# Game_of_Simon.net
KiCad netlist of a schematic drawn in Altium Designer
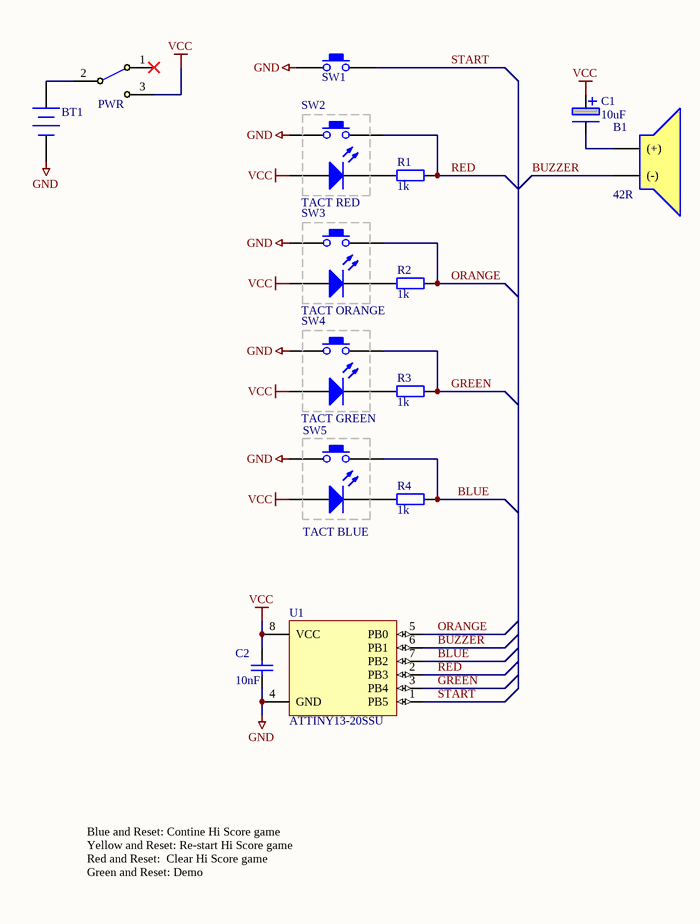
[diagram p0: Game of Simon.SchDoc]

(export (version "E")
  (design (tool "Eeschema 10.0.6"))
  (components
    (comp (ref "B1") (value "42R") (footprint "BUZZER") (libsource (lib "Simon Says") (part "BUZZER")))
    (comp (ref "BT1")
      (value "CR2032 Battery Holder")
      (footprint "Simon Says:CR2032 HOLDER")
      (description "CR2032 Battery Holder, Through Hole, Horizontal Mount")
      (libsource (lib "FavoritesLibrary") (part "SYM-19301741-1"))
    )
    (comp (ref "C1")
      (value "10uF")
      (footprint "Simon Says:CAP ELECTRO 5mm")
      (description "5mm Through Hole Electrolytic 2mm Pitch, 5mm height")
      (libsource (lib "FavoritesLibrary") (part "SYM-su2zmkw1kc3z49ns9isd-1"))
    )
    (comp (ref "C2")
      (value "10nF")
      (footprint "Simon Says:CAP 0.100\"")
      (description "Capacitor, Ceramic, 10000pF, 50VDC, 20-% Tol, 20+% Tol, X7R-TC Code, -15, 15%-TC")
      (fields (field (name "MANUFACTURER PART NUMBER") "C315C103M5R5TA"))
      (libsource (lib "FavoritesLibrary") (part "SYM-f9eb30fd1b76262c-1"))
    )
    (comp (ref "PWR")
      (value "SS12D00G3")
      (footprint "SS12D00G3")
      (description "SS12D00G3 Toggle Switch")
      (libsource (lib "Schlib1") (part "SS12D00G3 Toggle Switch"))
    )
    (comp (ref "R1")
      (value "1k")
      (footprint "Simon Says:RESISTOR 0.400\"")
      (description "RESISITOR THROUGH HOLE 1/4W")
      (libsource (lib "FavoritesLibrary") (part "SYM-iaxfckaaxq3jb0c9euu5-1"))
    )
    (comp (ref "R2")
      (value "1k")
      (footprint "Simon Says:RESISTOR 0.400\"")
      (description "RESISITOR THROUGH HOLE 1/4W")
      (libsource (lib "FavoritesLibrary") (part "SYM-iaxfckaaxq3jb0c9euu5-1"))
    )
    (comp (ref "R3")
      (value "1k")
      (footprint "Simon Says:RESISTOR 0.400\"")
      (description "RESISITOR THROUGH HOLE 1/4W")
      (libsource (lib "FavoritesLibrary") (part "SYM-iaxfckaaxq3jb0c9euu5-1"))
    )
    (comp (ref "R4")
      (value "1k")
      (footprint "Simon Says:RESISTOR 0.400\"")
      (description "RESISITOR THROUGH HOLE 1/4W")
      (libsource (lib "FavoritesLibrary") (part "SYM-iaxfckaaxq3jb0c9euu5-1"))
    )
    (comp (ref "SW1")
      (value "12MM TACT SWITCH")
      (footprint "12mm TACT THROUGH HOLE")
      (libsource (lib "Simon Says") (part "12MM TACT SWITCH"))
    )
    (comp (ref "SW2")
      (value "TACT RED")
      (footprint "ILLUMINATED TACT RED")
      (description "12mm TACT SWITCH RED")
      (libsource (lib "Simon Says") (part "TACT RED"))
    )
    (comp (ref "SW3")
      (value "TACT ORANGE")
      (footprint "ILLUMINATED TACT ORANGE")
      (description "12mm TACT SWITCH ORANGE")
      (libsource (lib "Simon Says") (part "TACT ORANGE"))
    )
    (comp (ref "SW4")
      (value "TACT GREEN")
      (footprint "ILLUMINATED TACT GREEN")
      (description "12mm TACT SWITCH GREEN")
      (libsource (lib "Simon Says") (part "TACT GREEN"))
    )
    (comp (ref "SW5")
      (value "TACT BLUE")
      (footprint "ILLUMINATED TACT BLUE")
      (description "ILLUMINATED 12MM TACT SWITCH (BLUE)")
      (libsource (lib "Simon Says") (part "TACT BLUE"))
    )
    (comp (ref "U1")
      (value "ATTINY13-20SSU")
      (footprint "DIP-8")
      (description "ATtiny Series 20 MHz 1 KB Flash 64 B SRAM 8-Bit Microcontroller - SOIC-8")
      (fields (field (name "MF") "Microchip"))
      (libsource (lib "Simon Says") (part "ATTINY13-20SSU"))
    )
  )
  (nets
    (net (code "1") (name "/BLUE") (class "Default")
      (node (ref "R4") (pin "2") (pinfunction "2_2") (pintype "passive"))
      (node (ref "SW5") (pin "2") (pinfunction "2_2") (pintype "passive"))
      (node (ref "U1") (pin "7") (pinfunction "PB2_7") (pintype "bidirectional"))
    )
    (net (code "2") (name "/BUZZER") (class "Default")
      (node (ref "B1") (pin "2") (pinfunction "(-)_2") (pintype "passive"))
      (node (ref "U1") (pin "6") (pinfunction "PB1_6") (pintype "bidirectional"))
    )
    (net (code "3") (name "/GREEN") (class "Default")
      (node (ref "R3") (pin "2") (pinfunction "2_2") (pintype "passive"))
      (node (ref "SW4") (pin "2") (pinfunction "2_2") (pintype "passive"))
      (node (ref "U1") (pin "3") (pinfunction "PB4_3") (pintype "bidirectional"))
    )
    (net (code "4") (name "/ORANGE") (class "Default")
      (node (ref "R2") (pin "2") (pinfunction "2_2") (pintype "passive"))
      (node (ref "SW3") (pin "2") (pinfunction "2_2") (pintype "passive"))
      (node (ref "U1") (pin "5") (pinfunction "PB0_5") (pintype "bidirectional"))
    )
    (net (code "5") (name "/RED") (class "Default")
      (node (ref "R1") (pin "2") (pinfunction "2_2") (pintype "passive"))
      (node (ref "SW2") (pin "2") (pinfunction "2_2") (pintype "passive"))
      (node (ref "U1") (pin "2") (pinfunction "PB3_2") (pintype "bidirectional"))
    )
    (net (code "6") (name "/START") (class "Default")
      (node (ref "SW1") (pin "2") (pinfunction "2_2") (pintype "passive"))
      (node (ref "U1") (pin "1") (pinfunction "PB5_1") (pintype "bidirectional"))
    )
    (net (code "7") (name "GND") (class "Default")
      (node (ref "BT1") (pin "2") (pinfunction "-_2") (pintype "passive"))
      (node (ref "C2") (pin "2") (pinfunction "2_2") (pintype "passive"))
      (node (ref "SW1") (pin "1") (pinfunction "1_1") (pintype "passive"))
      (node (ref "SW2") (pin "1") (pinfunction "1_1") (pintype "passive"))
      (node (ref "SW3") (pin "1") (pinfunction "1_1") (pintype "passive"))
      (node (ref "SW4") (pin "1") (pinfunction "1_1") (pintype "passive"))
      (node (ref "SW5") (pin "1") (pinfunction "1_1") (pintype "passive"))
      (node (ref "U1") (pin "4") (pinfunction "GND_4") (pintype "passive"))
    )
    (net (code "8") (name "Net-(B1-(+))") (class "Default")
      (node (ref "B1") (pin "1") (pinfunction "(+)_1") (pintype "passive"))
      (node (ref "C1") (pin "2") (pinfunction "2_2") (pintype "passive"))
    )
    (net (code "9") (name "Net-(BT1-+)") (class "Default")
      (node (ref "BT1") (pin "1") (pinfunction "+_1") (pintype "passive"))
      (node (ref "PWR") (pin "2") (pinfunction "2_2") (pintype "passive"))
    )
    (net (code "10") (name "Net-(R1-Pad1)") (class "Default")
      (node (ref "R1") (pin "1") (pinfunction "1_1") (pintype "passive"))
      (node (ref "SW2") (pin "A") (pinfunction "A_A") (pintype "passive"))
    )
    (net (code "11") (name "Net-(R2-Pad1)") (class "Default")
      (node (ref "R2") (pin "1") (pinfunction "1_1") (pintype "passive"))
      (node (ref "SW3") (pin "A") (pinfunction "A_A") (pintype "passive"))
    )
    (net (code "12") (name "Net-(R3-Pad1)") (class "Default")
      (node (ref "R3") (pin "1") (pinfunction "1_1") (pintype "passive"))
      (node (ref "SW4") (pin "A") (pinfunction "A_A") (pintype "passive"))
    )
    (net (code "13") (name "Net-(R4-Pad1)") (class "Default")
      (node (ref "R4") (pin "1") (pinfunction "1_1") (pintype "passive"))
      (node (ref "SW5") (pin "A") (pinfunction "A_A") (pintype "passive"))
    )
    (net (code "14") (name "VCC") (class "Default")
      (node (ref "C1") (pin "1") (pinfunction "1_1") (pintype "passive"))
      (node (ref "C2") (pin "1") (pinfunction "1_1") (pintype "passive"))
      (node (ref "PWR") (pin "3") (pinfunction "3_3") (pintype "passive"))
      (node (ref "SW2") (pin "K") (pinfunction "K_K") (pintype "passive"))
      (node (ref "SW3") (pin "K") (pinfunction "K_K") (pintype "passive"))
      (node (ref "SW4") (pin "K") (pinfunction "K_K") (pintype "passive"))
      (node (ref "SW5") (pin "K") (pinfunction "K_K") (pintype "passive"))
      (node (ref "U1") (pin "8") (pinfunction "VCC_8") (pintype "power_in"))
    )
    (net (code "15") (name "unconnected-(PWR-Pad1)") (class "Default")
      (node (ref "PWR") (pin "1") (pinfunction "1_1") (pintype "passive+no_connect"))
    )
  )
)
